# IMU.net
KiCad netlist of a schematic drawn in Altium Designer
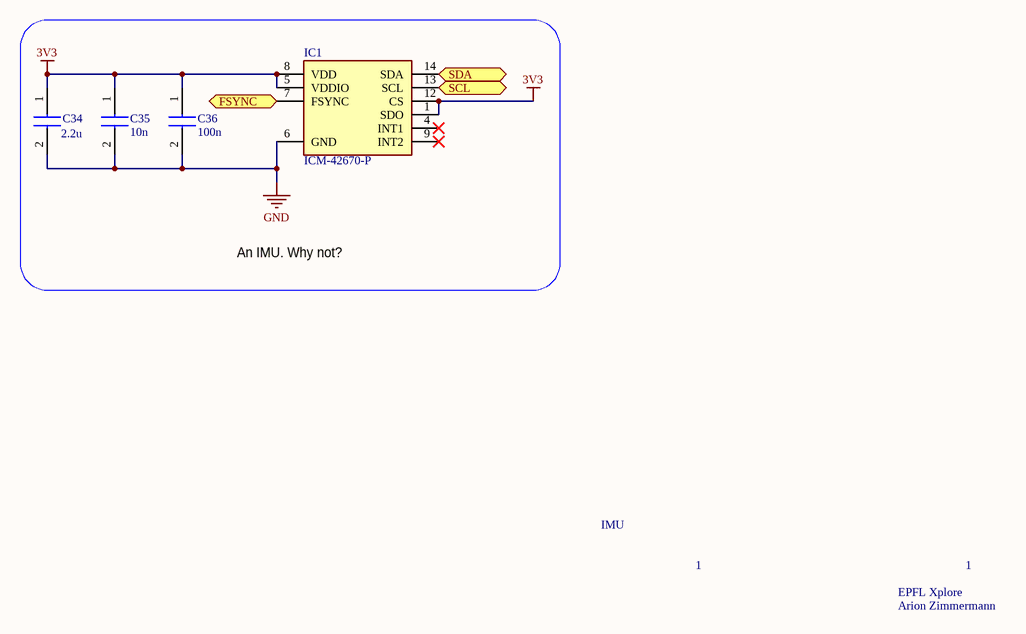
[diagram p0: IMU.SchDoc]

(export (version "E")
  (design (tool "Eeschema 10.0.6"))
  (components
    (comp (ref "C34")
      (value "2.2u")
      (footprint "C1206")
      (description "Capacitor")
      (fields
        (field (name "MANUFACTURER_PART_NUMBER") "C1206C106K4RACTU")
        (field (name "MOUSER PART NUMBER") "80-C1206C106K4R")
      )
      (libsource (lib "SamacSys") (part "C1206C106K4RACTU"))
    )
    (comp (ref "C35")
      (value "10n")
      (footprint "CAPC1608X95N")
      (description "Capacitor")
      (fields
        (field (name "MANUFACTURER_PART_NUMBER") "C0603C104K5RACTU")
        (field (name "MOUSER PART NUMBER") "80-C0603C104K5R")
      )
      (libsource (lib "CarrierBoard") (part "C0603C104K5RACTU"))
    )
    (comp (ref "C36")
      (value "100n")
      (footprint "CAPC1608X95N")
      (description "Capacitor")
      (fields
        (field (name "MANUFACTURER_PART_NUMBER") "C0603C104K5RACTU")
        (field (name "MOUSER PART NUMBER") "80-C0603C104K5R")
      )
      (libsource (lib "CarrierBoard") (part "C0603C104K5RACTU"))
    )
    (comp (ref "IC1")
      (value "ICM-42670-P")
      (footprint "ICM42670P")
      (description "Integrated Circuit")
      (fields (field (name "MOUSER PART NUMBER") "410-ICM-42670-P"))
      (libsource (lib "Pollux III_1") (part "ICM-42670-P"))
    )
  )
  (nets
    (net (code "1") (name "/FSYNC") (class "Default")
      (node (ref "IC1") (pin "7") (pinfunction "FSYNC_7") (pintype "passive"))
    )
    (net (code "2") (name "/SCL") (class "Default")
      (node (ref "IC1") (pin "13") (pinfunction "SCL_13") (pintype "passive"))
    )
    (net (code "3") (name "/SDA") (class "Default")
      (node (ref "IC1") (pin "14") (pinfunction "SDA_14") (pintype "passive"))
    )
    (net (code "4") (name "3V3") (class "Default")
      (node (ref "C34") (pin "1") (pinfunction "1_1") (pintype "passive"))
      (node (ref "C35") (pin "1") (pinfunction "1_1") (pintype "passive"))
      (node (ref "C36") (pin "1") (pinfunction "1_1") (pintype "passive"))
      (node (ref "IC1") (pin "1") (pinfunction "SDO_1") (pintype "passive"))
      (node (ref "IC1") (pin "12") (pinfunction "CS_12") (pintype "passive"))
      (node (ref "IC1") (pin "5") (pinfunction "VDDIO_5") (pintype "passive"))
      (node (ref "IC1") (pin "8") (pinfunction "VDD_8") (pintype "passive"))
    )
    (net (code "5") (name "GND") (class "Default")
      (node (ref "C34") (pin "2") (pinfunction "2_2") (pintype "passive"))
      (node (ref "C35") (pin "2") (pinfunction "2_2") (pintype "passive"))
      (node (ref "C36") (pin "2") (pinfunction "2_2") (pintype "passive"))
      (node (ref "IC1") (pin "6") (pinfunction "GND_6") (pintype "passive"))
    )
    (net (code "6") (name "unconnected-(IC1-INT1-Pad4)") (class "Default")
      (node (ref "IC1") (pin "4") (pinfunction "INT1_4") (pintype "passive+no_connect"))
    )
    (net (code "7") (name "unconnected-(IC1-INT2-Pad9)") (class "Default")
      (node (ref "IC1") (pin "9") (pinfunction "INT2_9") (pintype "passive+no_connect"))
    )
  )
)
